# X13_Power_Distribution_C.net
KiCad netlist of a schematic drawn in EAGLE
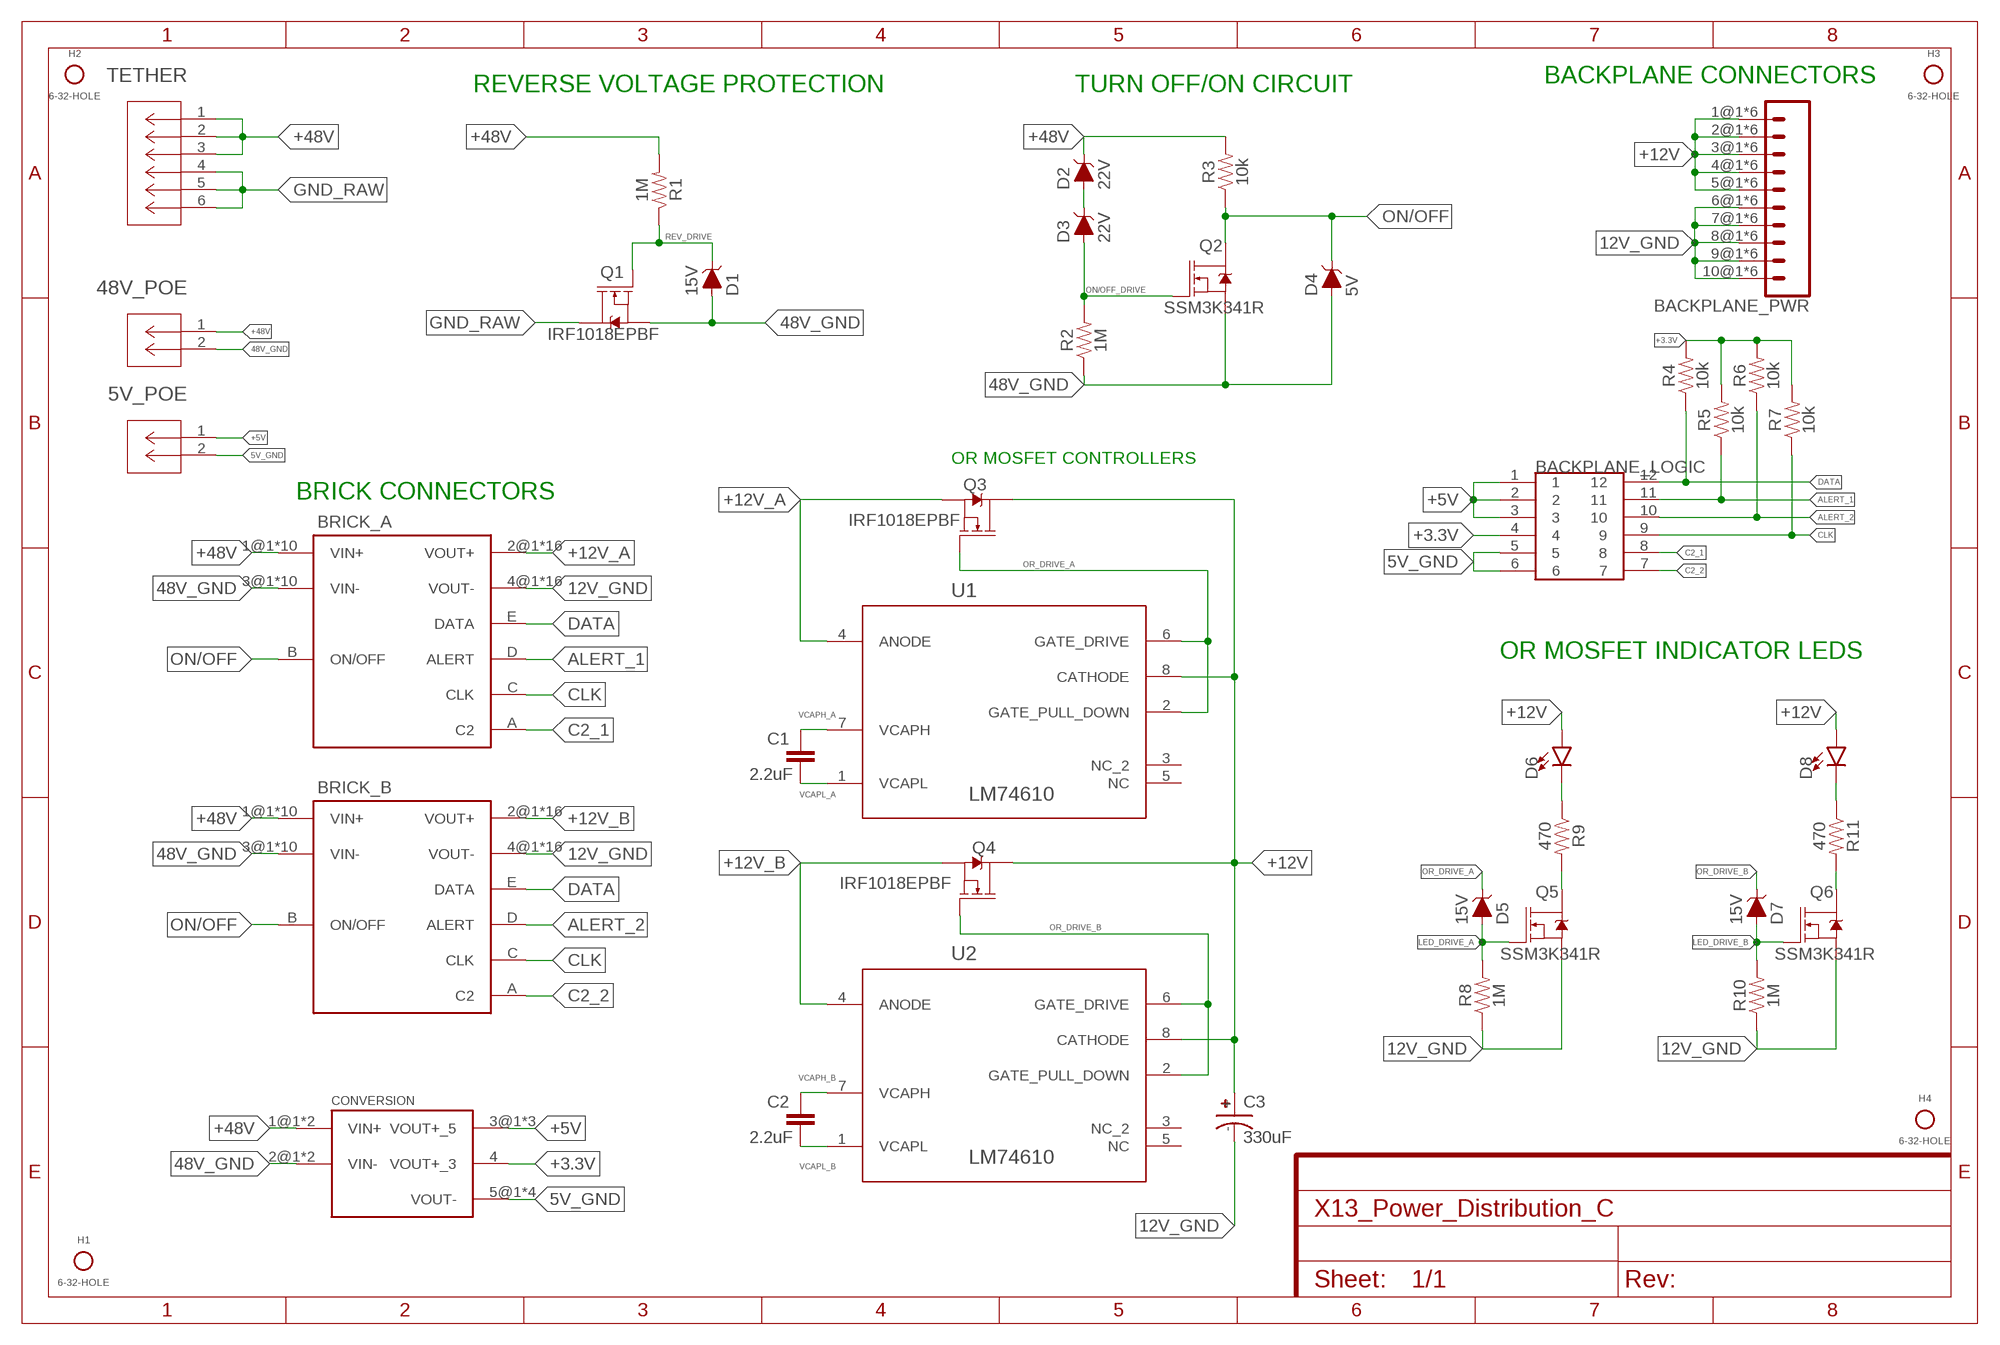
[diagram p0: schematic, sheet 1, part 1 of 2]
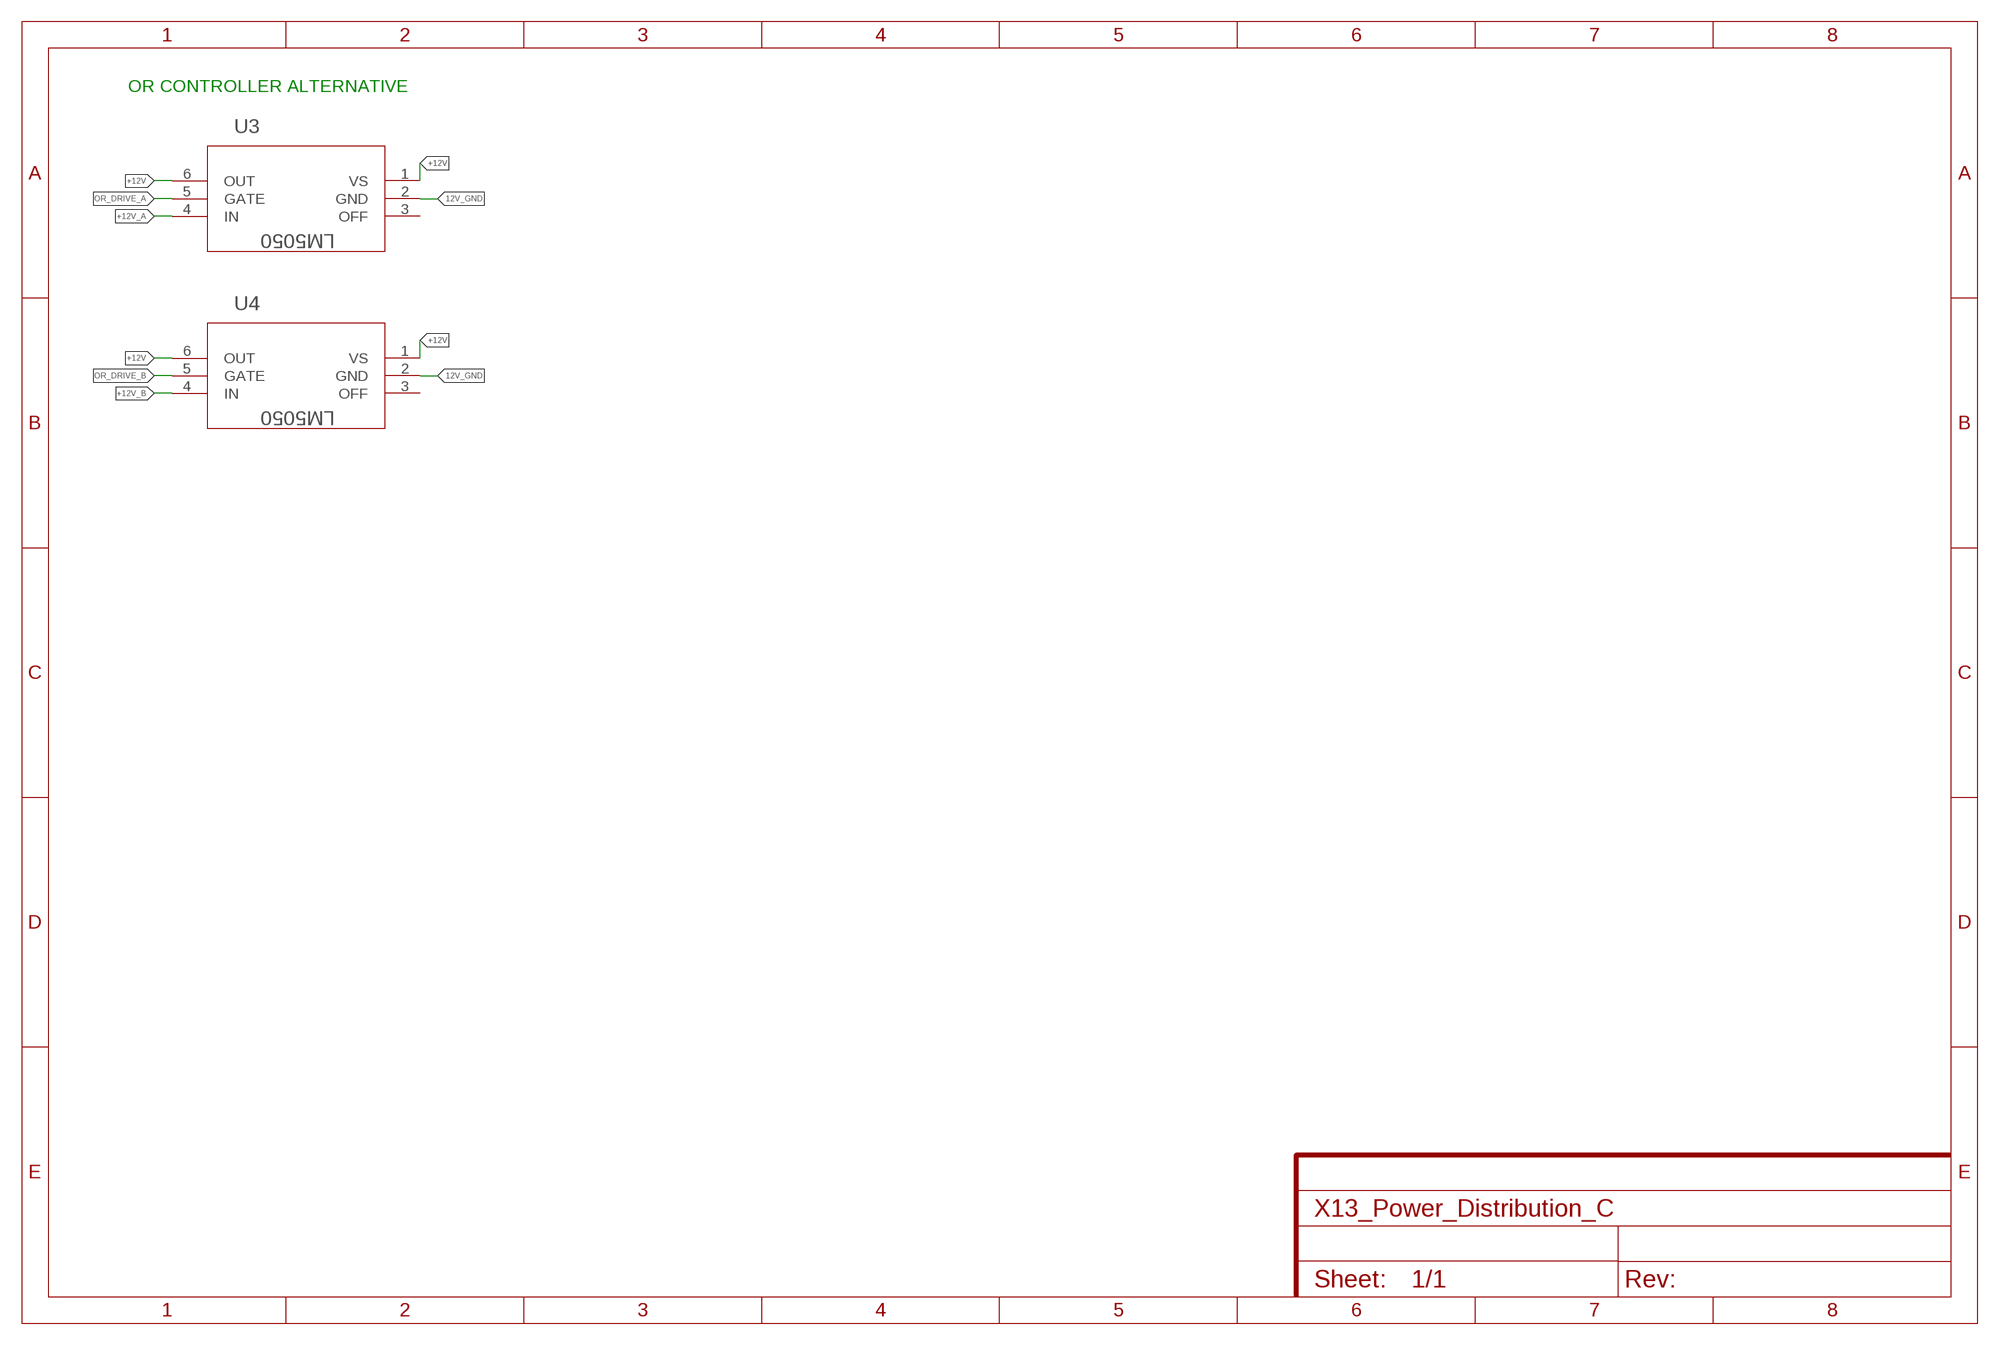
[diagram p1: schematic, sheet 1, part 2 of 2]

(export (version "E")
  (design (tool "Eeschema 10.0.6"))
  (components
    (comp (ref "5V_POE")
      (value "POE_TERMINAL")
      (footprint "eagle-import:CONN2_282834-2_TEC")
      (fields
        (field (name "MANUFACTURER_PART_NUMBER") "282834-2")
        (field (name "COPYRIGHT") "Copyright (C) 2016 Accelerated Designs. All rights reserved")
      )
      (libsource (lib "eagle-import") (part "POE_TERMINAL"))
    )
    (comp (ref "48V_POE")
      (value "POE_TERMINAL")
      (footprint "eagle-import:CONN2_282834-2_TEC")
      (fields
        (field (name "MANUFACTURER_PART_NUMBER") "282834-2")
        (field (name "COPYRIGHT") "Copyright (C) 2016 Accelerated Designs. All rights reserved")
      )
      (libsource (lib "eagle-import") (part "POE_TERMINAL"))
    )
    (comp (ref "BACKPLANE_LOGIC")
      (value "IPL1-106-01-L-D-RE1-K")
      (footprint "eagle-import:IPL1-106-01-L-D-RE1-K")
      (libsource (lib "eagle-import") (part "IPL1-106-01-L-D-RE1-K"))
    )
    (comp (ref "BACKPLANE_PWR")
      (value "MPPT-10-01-01-L-RA-SD")
      (footprint "eagle-import:MPPT-10-01-01-L-RA-SD")
      (libsource (lib "eagle-import") (part "MPPT-10-01-01-L-RA-SD"))
    )
    (comp (ref "BRICK_A")
      (value "DIST2BRICK_C")
      (footprint "eagle-import:DIST2BRICK_C")
      (libsource (lib "eagle-import") (part "DIST2BRICK_C"))
    )
    (comp (ref "BRICK_B")
      (value "DIST2BRICK_C")
      (footprint "eagle-import:DIST2BRICK_C")
      (libsource (lib "eagle-import") (part "DIST2BRICK_C"))
    )
    (comp (ref "C1")
      (value "2.2uF")
      (footprint "eagle-import:0603")
      (libsource (lib "eagle-import") (part "0.1UF-0603-100V-10%"))
    )
    (comp (ref "C2")
      (value "2.2uF")
      (footprint "eagle-import:0603")
      (libsource (lib "eagle-import") (part "0.1UF-0603-100V-10%"))
    )
    (comp (ref "C3")
      (value "330uF")
      (footprint "eagle-import:CAPAE1030X1050N")
      (fields
        (field (name "ARROW_PART_NUMBER") "UCM1H331MNL1GS")
        (field (name "MOUSER_PART_NUMBER") "647-UCM1H331MNL1GS")
      )
      (libsource (lib "eagle-import") (part "UCM1H331MNL1GS"))
    )
    (comp (ref "CONVERSION")
      (value "DIST2CON")
      (footprint "eagle-import:DIST2CON")
      (libsource (lib "eagle-import") (part "DIST2CON"))
    )
    (comp (ref "D1")
      (value "15V")
      (footprint "eagle-import:SOD-323")
      (libsource (lib "eagle-import") (part "DIODE-ZENER-BZT52C3V6S"))
    )
    (comp (ref "D2")
      (value "22V")
      (footprint "eagle-import:SOD-323")
      (libsource (lib "eagle-import") (part "DIODE-ZENER-BZT52C3V6S"))
    )
    (comp (ref "D3")
      (value "22V")
      (footprint "eagle-import:SOD-323")
      (libsource (lib "eagle-import") (part "DIODE-ZENER-BZT52C3V6S"))
    )
    (comp (ref "D4")
      (value "5V")
      (footprint "eagle-import:SOD-323")
      (libsource (lib "eagle-import") (part "DIODE-ZENER-BZT52C3V6S"))
    )
    (comp (ref "D5")
      (value "15V")
      (footprint "eagle-import:SOD-323")
      (libsource (lib "eagle-import") (part "DIODE-ZENER-BZT52C3V6S"))
    )
    (comp (ref "D6")
      (value "LED0603")
      (footprint "eagle-import:LED-0603")
      (libsource (lib "eagle-import") (part "LED0603"))
    )
    (comp (ref "D7")
      (value "15V")
      (footprint "eagle-import:SOD-323")
      (libsource (lib "eagle-import") (part "DIODE-ZENER-BZT52C3V6S"))
    )
    (comp (ref "D8")
      (value "LED0603")
      (footprint "eagle-import:LED-0603")
      (libsource (lib "eagle-import") (part "LED0603"))
    )
    (comp (ref "H1")
      (value "6-32-HOLE")
      (footprint "eagle-import:6-32-HOLE")
      (libsource (lib "eagle-import") (part "6-32-HOLE"))
    )
    (comp (ref "H2")
      (value "6-32-HOLE")
      (footprint "eagle-import:6-32-HOLE")
      (libsource (lib "eagle-import") (part "6-32-HOLE"))
    )
    (comp (ref "H3")
      (value "6-32-HOLE")
      (footprint "eagle-import:6-32-HOLE")
      (libsource (lib "eagle-import") (part "6-32-HOLE"))
    )
    (comp (ref "H4")
      (value "6-32-HOLE")
      (footprint "eagle-import:6-32-HOLE")
      (libsource (lib "eagle-import") (part "6-32-HOLE"))
    )
    (comp (ref "Q1")
      (value "IRF1018EPBF")
      (footprint "eagle-import:TO263")
      (libsource (lib "eagle-import") (part "IRF1018EPBF"))
    )
    (comp (ref "Q2")
      (value "SSM3K341R")
      (footprint "eagle-import:SOT323")
      (libsource (lib "eagle-import") (part "MOSFET-NCH-2N7002PW"))
    )
    (comp (ref "Q3")
      (value "IRF1018EPBF")
      (footprint "eagle-import:TO263")
      (libsource (lib "eagle-import") (part "IRF1018EPBF"))
    )
    (comp (ref "Q4")
      (value "IRF1018EPBF")
      (footprint "eagle-import:TO263")
      (libsource (lib "eagle-import") (part "IRF1018EPBF"))
    )
    (comp (ref "Q5")
      (value "SSM3K341R")
      (footprint "eagle-import:SOT323")
      (libsource (lib "eagle-import") (part "MOSFET-NCH-2N7002PW"))
    )
    (comp (ref "Q6")
      (value "SSM3K341R")
      (footprint "eagle-import:SOT323")
      (libsource (lib "eagle-import") (part "MOSFET-NCH-2N7002PW"))
    )
    (comp (ref "R1")
      (value "1M")
      (footprint "eagle-import:0603")
      (libsource (lib "eagle-import") (part "RESISTOR0603"))
    )
    (comp (ref "R2")
      (value "1M")
      (footprint "eagle-import:0603")
      (fields (field (name "SPICEPREFIX") "R"))
      (libsource (lib "eagle-import") (part "RESISTOR0603"))
    )
    (comp (ref "R3")
      (value "10k")
      (footprint "eagle-import:0603")
      (fields (field (name "SPICEPREFIX") "R"))
      (libsource (lib "eagle-import") (part "RESISTOR0603"))
    )
    (comp (ref "R4")
      (value "10k")
      (footprint "eagle-import:0603")
      (libsource (lib "eagle-import") (part "RESISTOR0603"))
    )
    (comp (ref "R5")
      (value "10k")
      (footprint "eagle-import:0603")
      (libsource (lib "eagle-import") (part "RESISTOR0603"))
    )
    (comp (ref "R6")
      (value "10k")
      (footprint "eagle-import:0603")
      (libsource (lib "eagle-import") (part "RESISTOR0603"))
    )
    (comp (ref "R7")
      (value "10k")
      (footprint "eagle-import:0603")
      (libsource (lib "eagle-import") (part "RESISTOR0603"))
    )
    (comp (ref "R8")
      (value "1M")
      (footprint "eagle-import:0603")
      (fields (field (name "SPICEPREFIX") "R"))
      (libsource (lib "eagle-import") (part "RESISTOR0603"))
    )
    (comp (ref "R9")
      (value "470")
      (footprint "eagle-import:0603")
      (libsource (lib "eagle-import") (part "RESISTOR0603"))
    )
    (comp (ref "R10")
      (value "1M")
      (footprint "eagle-import:0603")
      (fields (field (name "SPICEPREFIX") "R"))
      (libsource (lib "eagle-import") (part "RESISTOR0603"))
    )
    (comp (ref "R11")
      (value "470")
      (footprint "eagle-import:0603")
      (libsource (lib "eagle-import") (part "RESISTOR0603"))
    )
    (comp (ref "TETHER")
      (value "48V")
      (footprint "eagle-import:CON6_P5MM_VER_TERM-BLK_TYC")
      (fields (field (name "MANUFACTURER_PART_NUMBER") "796636-6"))
      (libsource (lib "eagle-import") (part "DIST_TO_TETHER"))
    )
    (comp (ref "U1")
      (value "LM74610")
      (footprint "eagle-import:DGK0008A_M")
      (fields (field (name "MANUFACTURER") "Texas Instruments") (field (name "PARTNUMBER") "LM74610QDGKRQ1"))
      (libsource (lib "eagle-import") (part "DIST_OR_DIODEDGK0008A_M"))
    )
    (comp (ref "U2")
      (value "LM74610")
      (footprint "eagle-import:DGK0008A_M")
      (fields (field (name "MANUFACTURER") "Texas Instruments") (field (name "PARTNUMBER") "LM74610QDGKRQ1"))
      (libsource (lib "eagle-import") (part "DIST_OR_DIODEDGK0008A_M"))
    )
    (comp (ref "U3")
      (value "LM5050")
      (footprint "eagle-import:MK06A-M")
      (fields
        (field (name "MANUFACTURER") "Texas Instruments")
        (field (name "MANUFACTURER_PART_NUMBER") "LM5050MK-1/NOPB")
      )
      (libsource (lib "eagle-import") (part "DIST_OR_CONTROL_ALTMK06A-M"))
    )
    (comp (ref "U4")
      (value "LM5050")
      (footprint "eagle-import:MK06A-M")
      (fields
        (field (name "MANUFACTURER") "Texas Instruments")
        (field (name "MANUFACTURER_PART_NUMBER") "LM5050MK-1/NOPB")
      )
      (libsource (lib "eagle-import") (part "DIST_OR_CONTROL_ALTMK06A-M"))
    )
  )
  (nets
    (net (code "1") (name "+3.3V") (class "Default")
      (node (ref "BACKPLANE_LOGIC") (pin "4") (pinfunction "4_4") (pintype "bidirectional"))
      (node (ref "CONVERSION") (pin "4") (pinfunction "VOUT+_3_4") (pintype "bidirectional"))
      (node (ref "R4") (pin "2") (pinfunction "2_2") (pintype "passive"))
      (node (ref "R5") (pin "2") (pinfunction "2_2") (pintype "passive"))
      (node (ref "R6") (pin "2") (pinfunction "2_2") (pintype "passive"))
      (node (ref "R7") (pin "2") (pinfunction "2_2") (pintype "passive"))
    )
    (net (code "2") (name "+5V") (class "Default")
      (node (ref "5V_POE") (pin "1") (pinfunction "1_1") (pintype "passive"))
      (node (ref "BACKPLANE_LOGIC") (pin "1") (pinfunction "1_1") (pintype "bidirectional"))
      (node (ref "BACKPLANE_LOGIC") (pin "2") (pinfunction "2_2") (pintype "bidirectional"))
      (node (ref "BACKPLANE_LOGIC") (pin "3") (pinfunction "3_3") (pintype "bidirectional"))
      (node (ref "CONVERSION") (pin "3@1") (pinfunction "VOUT+_5_3@1") (pintype "bidirectional"))
      (node (ref "CONVERSION") (pin "3@2") (pinfunction "VOUT+_5_3@2") (pintype "bidirectional"))
      (node (ref "CONVERSION") (pin "3@3") (pinfunction "VOUT+_5_3@3") (pintype "bidirectional"))
    )
    (net (code "3") (name "+12V") (class "Default")
      (node (ref "BACKPLANE_PWR") (pin "1@1") (pinfunction "1_1@1") (pintype "passive"))
      (node (ref "BACKPLANE_PWR") (pin "1@2") (pinfunction "1_1@2") (pintype "passive"))
      (node (ref "BACKPLANE_PWR") (pin "1@3") (pinfunction "1_1@3") (pintype "passive"))
      (node (ref "BACKPLANE_PWR") (pin "1@4") (pinfunction "1_1@4") (pintype "passive"))
      (node (ref "BACKPLANE_PWR") (pin "1@5") (pinfunction "1_1@5") (pintype "passive"))
      (node (ref "BACKPLANE_PWR") (pin "1@6") (pinfunction "1_1@6") (pintype "passive"))
      (node (ref "BACKPLANE_PWR") (pin "2@1") (pinfunction "2_2@1") (pintype "passive"))
      (node (ref "BACKPLANE_PWR") (pin "2@2") (pinfunction "2_2@2") (pintype "passive"))
      (node (ref "BACKPLANE_PWR") (pin "2@3") (pinfunction "2_2@3") (pintype "passive"))
      (node (ref "BACKPLANE_PWR") (pin "2@4") (pinfunction "2_2@4") (pintype "passive"))
      (node (ref "BACKPLANE_PWR") (pin "2@5") (pinfunction "2_2@5") (pintype "passive"))
      (node (ref "BACKPLANE_PWR") (pin "2@6") (pinfunction "2_2@6") (pintype "passive"))
      (node (ref "BACKPLANE_PWR") (pin "3@1") (pinfunction "3_3@1") (pintype "passive"))
      (node (ref "BACKPLANE_PWR") (pin "3@2") (pinfunction "3_3@2") (pintype "passive"))
      (node (ref "BACKPLANE_PWR") (pin "3@3") (pinfunction "3_3@3") (pintype "passive"))
      (node (ref "BACKPLANE_PWR") (pin "3@4") (pinfunction "3_3@4") (pintype "passive"))
      (node (ref "BACKPLANE_PWR") (pin "3@5") (pinfunction "3_3@5") (pintype "passive"))
      (node (ref "BACKPLANE_PWR") (pin "3@6") (pinfunction "3_3@6") (pintype "passive"))
      (node (ref "BACKPLANE_PWR") (pin "4@1") (pinfunction "4_4@1") (pintype "passive"))
      (node (ref "BACKPLANE_PWR") (pin "4@2") (pinfunction "4_4@2") (pintype "passive"))
      (node (ref "BACKPLANE_PWR") (pin "4@3") (pinfunction "4_4@3") (pintype "passive"))
      (node (ref "BACKPLANE_PWR") (pin "4@4") (pinfunction "4_4@4") (pintype "passive"))
      (node (ref "BACKPLANE_PWR") (pin "4@5") (pinfunction "4_4@5") (pintype "passive"))
      (node (ref "BACKPLANE_PWR") (pin "4@6") (pinfunction "4_4@6") (pintype "passive"))
      (node (ref "BACKPLANE_PWR") (pin "5@1") (pinfunction "5_5@1") (pintype "passive"))
      (node (ref "BACKPLANE_PWR") (pin "5@2") (pinfunction "5_5@2") (pintype "passive"))
      (node (ref "BACKPLANE_PWR") (pin "5@3") (pinfunction "5_5@3") (pintype "passive"))
      (node (ref "BACKPLANE_PWR") (pin "5@4") (pinfunction "5_5@4") (pintype "passive"))
      (node (ref "BACKPLANE_PWR") (pin "5@5") (pinfunction "5_5@5") (pintype "passive"))
      (node (ref "BACKPLANE_PWR") (pin "5@6") (pinfunction "5_5@6") (pintype "passive"))
      (node (ref "C3") (pin "+") (pinfunction "+_+") (pintype "bidirectional"))
      (node (ref "D6") (pin "A") (pinfunction "A_A") (pintype "passive"))
      (node (ref "D8") (pin "A") (pinfunction "A_A") (pintype "passive"))
      (node (ref "Q3") (pin "3") (pinfunction "D_3") (pintype "bidirectional"))
      (node (ref "Q4") (pin "3") (pinfunction "D_3") (pintype "bidirectional"))
      (node (ref "U1") (pin "8") (pinfunction "CATHODE_8") (pintype "output"))
      (node (ref "U2") (pin "8") (pinfunction "CATHODE_8") (pintype "output"))
      (node (ref "U3") (pin "1") (pinfunction "VS_1") (pintype "passive"))
      (node (ref "U3") (pin "6") (pinfunction "OUT_6") (pintype "output"))
      (node (ref "U4") (pin "1") (pinfunction "VS_1") (pintype "passive"))
      (node (ref "U4") (pin "6") (pinfunction "OUT_6") (pintype "output"))
    )
    (net (code "4") (name "+12V_A") (class "Default")
      (node (ref "BRICK_A") (pin "2@1") (pinfunction "VOUT+_2@1") (pintype "bidirectional"))
      (node (ref "BRICK_A") (pin "2@10") (pinfunction "VOUT+_2@10") (pintype "bidirectional"))
      (node (ref "BRICK_A") (pin "2@11") (pinfunction "VOUT+_2@11") (pintype "bidirectional"))
      (node (ref "BRICK_A") (pin "2@12") (pinfunction "VOUT+_2@12") (pintype "bidirectional"))
      (node (ref "BRICK_A") (pin "2@13") (pinfunction "VOUT+_2@13") (pintype "bidirectional"))
      (node (ref "BRICK_A") (pin "2@14") (pinfunction "VOUT+_2@14") (pintype "bidirectional"))
      (node (ref "BRICK_A") (pin "2@15") (pinfunction "VOUT+_2@15") (pintype "bidirectional"))
      (node (ref "BRICK_A") (pin "2@16") (pinfunction "VOUT+_2@16") (pintype "bidirectional"))
      (node (ref "BRICK_A") (pin "2@2") (pinfunction "VOUT+_2@2") (pintype "bidirectional"))
      (node (ref "BRICK_A") (pin "2@3") (pinfunction "VOUT+_2@3") (pintype "bidirectional"))
      (node (ref "BRICK_A") (pin "2@4") (pinfunction "VOUT+_2@4") (pintype "bidirectional"))
      (node (ref "BRICK_A") (pin "2@5") (pinfunction "VOUT+_2@5") (pintype "bidirectional"))
      (node (ref "BRICK_A") (pin "2@6") (pinfunction "VOUT+_2@6") (pintype "bidirectional"))
      (node (ref "BRICK_A") (pin "2@7") (pinfunction "VOUT+_2@7") (pintype "bidirectional"))
      (node (ref "BRICK_A") (pin "2@8") (pinfunction "VOUT+_2@8") (pintype "bidirectional"))
      (node (ref "BRICK_A") (pin "2@9") (pinfunction "VOUT+_2@9") (pintype "bidirectional"))
      (node (ref "Q3") (pin "2") (pinfunction "S_2") (pintype "bidirectional"))
      (node (ref "U1") (pin "4") (pinfunction "ANODE_4") (pintype "power_in"))
      (node (ref "U3") (pin "4") (pinfunction "IN_4") (pintype "input"))
    )
    (net (code "5") (name "+12V_B") (class "Default")
      (node (ref "BRICK_B") (pin "2@1") (pinfunction "VOUT+_2@1") (pintype "bidirectional"))
      (node (ref "BRICK_B") (pin "2@10") (pinfunction "VOUT+_2@10") (pintype "bidirectional"))
      (node (ref "BRICK_B") (pin "2@11") (pinfunction "VOUT+_2@11") (pintype "bidirectional"))
      (node (ref "BRICK_B") (pin "2@12") (pinfunction "VOUT+_2@12") (pintype "bidirectional"))
      (node (ref "BRICK_B") (pin "2@13") (pinfunction "VOUT+_2@13") (pintype "bidirectional"))
      (node (ref "BRICK_B") (pin "2@14") (pinfunction "VOUT+_2@14") (pintype "bidirectional"))
      (node (ref "BRICK_B") (pin "2@15") (pinfunction "VOUT+_2@15") (pintype "bidirectional"))
      (node (ref "BRICK_B") (pin "2@16") (pinfunction "VOUT+_2@16") (pintype "bidirectional"))
      (node (ref "BRICK_B") (pin "2@2") (pinfunction "VOUT+_2@2") (pintype "bidirectional"))
      (node (ref "BRICK_B") (pin "2@3") (pinfunction "VOUT+_2@3") (pintype "bidirectional"))
      (node (ref "BRICK_B") (pin "2@4") (pinfunction "VOUT+_2@4") (pintype "bidirectional"))
      (node (ref "BRICK_B") (pin "2@5") (pinfunction "VOUT+_2@5") (pintype "bidirectional"))
      (node (ref "BRICK_B") (pin "2@6") (pinfunction "VOUT+_2@6") (pintype "bidirectional"))
      (node (ref "BRICK_B") (pin "2@7") (pinfunction "VOUT+_2@7") (pintype "bidirectional"))
      (node (ref "BRICK_B") (pin "2@8") (pinfunction "VOUT+_2@8") (pintype "bidirectional"))
      (node (ref "BRICK_B") (pin "2@9") (pinfunction "VOUT+_2@9") (pintype "bidirectional"))
      (node (ref "Q4") (pin "2") (pinfunction "S_2") (pintype "bidirectional"))
      (node (ref "U2") (pin "4") (pinfunction "ANODE_4") (pintype "power_in"))
      (node (ref "U4") (pin "4") (pinfunction "IN_4") (pintype "input"))
    )
    (net (code "6") (name "+48V") (class "Default")
      (node (ref "48V_POE") (pin "1") (pinfunction "1_1") (pintype "passive"))
      (node (ref "BRICK_A") (pin "1@1") (pinfunction "VIN+_1@1") (pintype "bidirectional"))
      (node (ref "BRICK_A") (pin "1@10") (pinfunction "VIN+_1@10") (pintype "bidirectional"))
      (node (ref "BRICK_A") (pin "1@2") (pinfunction "VIN+_1@2") (pintype "bidirectional"))
      (node (ref "BRICK_A") (pin "1@3") (pinfunction "VIN+_1@3") (pintype "bidirectional"))
      (node (ref "BRICK_A") (pin "1@4") (pinfunction "VIN+_1@4") (pintype "bidirectional"))
      (node (ref "BRICK_A") (pin "1@5") (pinfunction "VIN+_1@5") (pintype "bidirectional"))
      (node (ref "BRICK_A") (pin "1@6") (pinfunction "VIN+_1@6") (pintype "bidirectional"))
      (node (ref "BRICK_A") (pin "1@7") (pinfunction "VIN+_1@7") (pintype "bidirectional"))
      (node (ref "BRICK_A") (pin "1@8") (pinfunction "VIN+_1@8") (pintype "bidirectional"))
      (node (ref "BRICK_A") (pin "1@9") (pinfunction "VIN+_1@9") (pintype "bidirectional"))
      (node (ref "BRICK_B") (pin "1@1") (pinfunction "VIN+_1@1") (pintype "bidirectional"))
      (node (ref "BRICK_B") (pin "1@10") (pinfunction "VIN+_1@10") (pintype "bidirectional"))
      (node (ref "BRICK_B") (pin "1@2") (pinfunction "VIN+_1@2") (pintype "bidirectional"))
      (node (ref "BRICK_B") (pin "1@3") (pinfunction "VIN+_1@3") (pintype "bidirectional"))
      (node (ref "BRICK_B") (pin "1@4") (pinfunction "VIN+_1@4") (pintype "bidirectional"))
      (node (ref "BRICK_B") (pin "1@5") (pinfunction "VIN+_1@5") (pintype "bidirectional"))
      (node (ref "BRICK_B") (pin "1@6") (pinfunction "VIN+_1@6") (pintype "bidirectional"))
      (node (ref "BRICK_B") (pin "1@7") (pinfunction "VIN+_1@7") (pintype "bidirectional"))
      (node (ref "BRICK_B") (pin "1@8") (pinfunction "VIN+_1@8") (pintype "bidirectional"))
      (node (ref "BRICK_B") (pin "1@9") (pinfunction "VIN+_1@9") (pintype "bidirectional"))
      (node (ref "CONVERSION") (pin "1@1") (pinfunction "VIN+_1@1") (pintype "bidirectional"))
      (node (ref "CONVERSION") (pin "1@2") (pinfunction "VIN+_1@2") (pintype "bidirectional"))
      (node (ref "D2") (pin "C") (pinfunction "C_C") (pintype "passive"))
      (node (ref "R1") (pin "2") (pinfunction "2_2") (pintype "passive"))
      (node (ref "R3") (pin "2") (pinfunction "2_2") (pintype "passive"))
      (node (ref "TETHER") (pin "1") (pinfunction "1_1") (pintype "passive"))
      (node (ref "TETHER") (pin "2") (pinfunction "2_2") (pintype "passive"))
      (node (ref "TETHER") (pin "3") (pinfunction "3_3") (pintype "passive"))
    )
    (net (code "7") (name "/ON{slash}OFF_DRIVE") (class "Default")
      (node (ref "D3") (pin "A") (pinfunction "A_A") (pintype "passive"))
      (node (ref "Q2") (pin "1") (pinfunction "G_1") (pintype "bidirectional"))
      (node (ref "R2") (pin "2") (pinfunction "2_2") (pintype "passive"))
    )
    (net (code "8") (name "/REV_DRIVE") (class "Default")
      (node (ref "D1") (pin "C") (pinfunction "C_C") (pintype "passive"))
      (node (ref "Q1") (pin "1") (pinfunction "G_1") (pintype "bidirectional"))
      (node (ref "R1") (pin "1") (pinfunction "1_1") (pintype "passive"))
    )
    (net (code "9") (name "/VCAPH_A") (class "Default")
      (node (ref "C1") (pin "1") (pinfunction "1_1") (pintype "passive"))
      (node (ref "U1") (pin "7") (pinfunction "VCAPH_7") (pintype "passive"))
    )
    (net (code "10") (name "/VCAPH_B") (class "Default")
      (node (ref "C2") (pin "1") (pinfunction "1_1") (pintype "passive"))
      (node (ref "U2") (pin "7") (pinfunction "VCAPH_7") (pintype "passive"))
    )
    (net (code "11") (name "/VCAPL_A") (class "Default")
      (node (ref "C1") (pin "2") (pinfunction "2_2") (pintype "passive"))
      (node (ref "U1") (pin "1") (pinfunction "VCAPL_1") (pintype "passive"))
    )
    (net (code "12") (name "/VCAPL_B") (class "Default")
      (node (ref "C2") (pin "2") (pinfunction "2_2") (pintype "passive"))
      (node (ref "U2") (pin "1") (pinfunction "VCAPL_1") (pintype "passive"))
    )
    (net (code "13") (name "5V_GND") (class "Default")
      (node (ref "5V_POE") (pin "2") (pinfunction "2_2") (pintype "passive"))
      (node (ref "BACKPLANE_LOGIC") (pin "5") (pinfunction "5_5") (pintype "bidirectional"))
      (node (ref "BACKPLANE_LOGIC") (pin "6") (pinfunction "6_6") (pintype "bidirectional"))
      (node (ref "CONVERSION") (pin "5@1") (pinfunction "VOUT-_5@1") (pintype "bidirectional"))
      (node (ref "CONVERSION") (pin "5@2") (pinfunction "VOUT-_5@2") (pintype "bidirectional"))
      (node (ref "CONVERSION") (pin "5@3") (pinfunction "VOUT-_5@3") (pintype "bidirectional"))
      (node (ref "CONVERSION") (pin "5@4") (pinfunction "VOUT-_5@4") (pintype "bidirectional"))
    )
    (net (code "14") (name "12V_GND") (class "Default")
      (node (ref "BACKPLANE_PWR") (pin "10@1") (pinfunction "10_10@1") (pintype "passive"))
      (node (ref "BACKPLANE_PWR") (pin "10@2") (pinfunction "10_10@2") (pintype "passive"))
      (node (ref "BACKPLANE_PWR") (pin "10@3") (pinfunction "10_10@3") (pintype "passive"))
      (node (ref "BACKPLANE_PWR") (pin "10@4") (pinfunction "10_10@4") (pintype "passive"))
      (node (ref "BACKPLANE_PWR") (pin "10@5") (pinfunction "10_10@5") (pintype "passive"))
      (node (ref "BACKPLANE_PWR") (pin "10@6") (pinfunction "10_10@6") (pintype "passive"))
      (node (ref "BACKPLANE_PWR") (pin "6@1") (pinfunction "6_6@1") (pintype "passive"))
      (node (ref "BACKPLANE_PWR") (pin "6@2") (pinfunction "6_6@2") (pintype "passive"))
      (node (ref "BACKPLANE_PWR") (pin "6@3") (pinfunction "6_6@3") (pintype "passive"))
      (node (ref "BACKPLANE_PWR") (pin "6@4") (pinfunction "6_6@4") (pintype "passive"))
      (node (ref "BACKPLANE_PWR") (pin "6@5") (pinfunction "6_6@5") (pintype "passive"))
      (node (ref "BACKPLANE_PWR") (pin "6@6") (pinfunction "6_6@6") (pintype "passive"))
      (node (ref "BACKPLANE_PWR") (pin "7@1") (pinfunction "7_7@1") (pintype "passive"))
      (node (ref "BACKPLANE_PWR") (pin "7@2") (pinfunction "7_7@2") (pintype "passive"))
      (node (ref "BACKPLANE_PWR") (pin "7@3") (pinfunction "7_7@3") (pintype "passive"))
      (node (ref "BACKPLANE_PWR") (pin "7@4") (pinfunction "7_7@4") (pintype "passive"))
      (node (ref "BACKPLANE_PWR") (pin "7@5") (pinfunction "7_7@5") (pintype "passive"))
      (node (ref "BACKPLANE_PWR") (pin "7@6") (pinfunction "7_7@6") (pintype "passive"))
      (node (ref "BACKPLANE_PWR") (pin "8@1") (pinfunction "8_8@1") (pintype "passive"))
      (node (ref "BACKPLANE_PWR") (pin "8@2") (pinfunction "8_8@2") (pintype "passive"))
      (node (ref "BACKPLANE_PWR") (pin "8@3") (pinfunction "8_8@3") (pintype "passive"))
      (node (ref "BACKPLANE_PWR") (pin "8@4") (pinfunction "8_8@4") (pintype "passive"))
      (node (ref "BACKPLANE_PWR") (pin "8@5") (pinfunction "8_8@5") (pintype "passive"))
      (node (ref "BACKPLANE_PWR") (pin "8@6") (pinfunction "8_8@6") (pintype "passive"))
      (node (ref "BACKPLANE_PWR") (pin "9@1") (pinfunction "9_9@1") (pintype "passive"))
      (node (ref "BACKPLANE_PWR") (pin "9@2") (pinfunction "9_9@2") (pintype "passive"))
      (node (ref "BACKPLANE_PWR") (pin "9@3") (pinfunction "9_9@3") (pintype "passive"))
      (node (ref "BACKPLANE_PWR") (pin "9@4") (pinfunction "9_9@4") (pintype "passive"))
      (node (ref "BACKPLANE_PWR") (pin "9@5") (pinfunction "9_9@5") (pintype "passive"))
      (node (ref "BACKPLANE_PWR") (pin "9@6") (pinfunction "9_9@6") (pintype "passive"))
      (node (ref "BRICK_A") (pin "4@1") (pinfunction "VOUT-_4@1") (pintype "bidirectional"))
      (node (ref "BRICK_A") (pin "4@10") (pinfunction "VOUT-_4@10") (pintype "bidirectional"))
      (node (ref "BRICK_A") (pin "4@11") (pinfunction "VOUT-_4@11") (pintype "bidirectional"))
      (node (ref "BRICK_A") (pin "4@12") (pinfunction "VOUT-_4@12") (pintype "bidirectional"))
      (node (ref "BRICK_A") (pin "4@13") (pinfunction "VOUT-_4@13") (pintype "bidirectional"))
      (node (ref "BRICK_A") (pin "4@14") (pinfunction "VOUT-_4@14") (pintype "bidirectional"))
      (node (ref "BRICK_A") (pin "4@15") (pinfunction "VOUT-_4@15") (pintype "bidirectional"))
      (node (ref "BRICK_A") (pin "4@16") (pinfunction "VOUT-_4@16") (pintype "bidirectional"))
      (node (ref "BRICK_A") (pin "4@2") (pinfunction "VOUT-_4@2") (pintype "bidirectional"))
      (node (ref "BRICK_A") (pin "4@3") (pinfunction "VOUT-_4@3") (pintype "bidirectional"))
      (node (ref "BRICK_A") (pin "4@4") (pinfunction "VOUT-_4@4") (pintype "bidirectional"))
      (node (ref "BRICK_A") (pin "4@5") (pinfunction "VOUT-_4@5") (pintype "bidirectional"))
      (node (ref "BRICK_A") (pin "4@6") (pinfunction "VOUT-_4@6") (pintype "bidirectional"))
      (node (ref "BRICK_A") (pin "4@7") (pinfunction "VOUT-_4@7") (pintype "bidirectional"))
      (node (ref "BRICK_A") (pin "4@8") (pinfunction "VOUT-_4@8") (pintype "bidirectional"))
      (node (ref "BRICK_A") (pin "4@9") (pinfunction "VOUT-_4@9") (pintype "bidirectional"))
      (node (ref "BRICK_B") (pin "4@1") (pinfunction "VOUT-_4@1") (pintype "bidirectional"))
      (node (ref "BRICK_B") (pin "4@10") (pinfunction "VOUT-_4@10") (pintype "bidirectional"))
      (node (ref "BRICK_B") (pin "4@11") (pinfunction "VOUT-_4@11") (pintype "bidirectional"))
      (node (ref "BRICK_B") (pin "4@12") (pinfunction "VOUT-_4@12") (pintype "bidirectional"))
      (node (ref "BRICK_B") (pin "4@13") (pinfunction "VOUT-_4@13") (pintype "bidirectional"))
      (node (ref "BRICK_B") (pin "4@14") (pinfunction "VOUT-_4@14") (pintype "bidirectional"))
      (node (ref "BRICK_B") (pin "4@15") (pinfunction "VOUT-_4@15") (pintype "bidirectional"))
      (node (ref "BRICK_B") (pin "4@16") (pinfunction "VOUT-_4@16") (pintype "bidirectional"))
      (node (ref "BRICK_B") (pin "4@2") (pinfunction "VOUT-_4@2") (pintype "bidirectional"))
      (node (ref "BRICK_B") (pin "4@3") (pinfunction "VOUT-_4@3") (pintype "bidirectional"))
      (node (ref "BRICK_B") (pin "4@4") (pinfunction "VOUT-_4@4") (pintype "bidirectional"))
      (node (ref "BRICK_B") (pin "4@5") (pinfunction "VOUT-_4@5") (pintype "bidirectional"))
      (node (ref "BRICK_B") (pin "4@6") (pinfunction "VOUT-_4@6") (pintype "bidirectional"))
      (node (ref "BRICK_B") (pin "4@7") (pinfunction "VOUT-_4@7") (pintype "bidirectional"))
      (node (ref "BRICK_B") (pin "4@8") (pinfunction "VOUT-_4@8") (pintype "bidirectional"))
      (node (ref "BRICK_B") (pin "4@9") (pinfunction "VOUT-_4@9") (pintype "bidirectional"))
      (node (ref "C3") (pin "-") (pinfunction "-_-") (pintype "bidirectional"))
      (node (ref "Q5") (pin "2") (pinfunction "S_2") (pintype "bidirectional"))
      (node (ref "Q6") (pin "2") (pinfunction "S_2") (pintype "bidirectional"))
      (node (ref "R10") (pin "1") (pinfunction "1_1") (pintype "passive"))
      (node (ref "R8") (pin "1") (pinfunction "1_1") (pintype "passive"))
      (node (ref "U3") (pin "2") (pinfunction "GND_2") (pintype "power_in"))
      (node (ref "U4") (pin "2") (pinfunction "GND_2") (pintype "power_in"))
    )
    (net (code "15") (name "48V_GND") (class "Default")
      (node (ref "48V_POE") (pin "2") (pinfunction "2_2") (pintype "passive"))
      (node (ref "BRICK_A") (pin "3@1") (pinfunction "VIN-_3@1") (pintype "bidirectional"))
      (node (ref "BRICK_A") (pin "3@10") (pinfunction "VIN-_3@10") (pintype "bidirectional"))
      (node (ref "BRICK_A") (pin "3@2") (pinfunction "VIN-_3@2") (pintype "bidirectional"))
      (node (ref "BRICK_A") (pin "3@3") (pinfunction "VIN-_3@3") (pintype "bidirectional"))
      (node (ref "BRICK_A") (pin "3@4") (pinfunction "VIN-_3@4") (pintype "bidirectional"))
      (node (ref "BRICK_A") (pin "3@5") (pinfunction "VIN-_3@5") (pintype "bidirectional"))
      (node (ref "BRICK_A") (pin "3@6") (pinfunction "VIN-_3@6") (pintype "bidirectional"))
      (node (ref "BRICK_A") (pin "3@7") (pinfunction "VIN-_3@7") (pintype "bidirectional"))
      (node (ref "BRICK_A") (pin "3@8") (pinfunction "VIN-_3@8") (pintype "bidirectional"))
      (node (ref "BRICK_A") (pin "3@9") (pinfunction "VIN-_3@9") (pintype "bidirectional"))
      (node (ref "BRICK_B") (pin "3@1") (pinfunction "VIN-_3@1") (pintype "bidirectional"))
      (node (ref "BRICK_B") (pin "3@10") (pinfunction "VIN-_3@10") (pintype "bidirectional"))
      (node (ref "BRICK_B") (pin "3@2") (pinfunction "VIN-_3@2") (pintype "bidirectional"))
      (node (ref "BRICK_B") (pin "3@3") (pinfunction "VIN-_3@3") (pintype "bidirectional"))
      (node (ref "BRICK_B") (pin "3@4") (pinfunction "VIN-_3@4") (pintype "bidirectional"))
      (node (ref "BRICK_B") (pin "3@5") (pinfunction "VIN-_3@5") (pintype "bidirectional"))
      (node (ref "BRICK_B") (pin "3@6") (pinfunction "VIN-_3@6") (pintype "bidirectional"))
      (node (ref "BRICK_B") (pin "3@7") (pinfunction "VIN-_3@7") (pintype "bidirectional"))
      (node (ref "BRICK_B") (pin "3@8") (pinfunction "VIN-_3@8") (pintype "bidirectional"))
      (node (ref "BRICK_B") (pin "3@9") (pinfunction "VIN-_3@9") (pintype "bidirectional"))
      (node (ref "CONVERSION") (pin "2@1") (pinfunction "VIN-_2@1") (pintype "bidirectional"))
      (node (ref "CONVERSION") (pin "2@2") (pinfunction "VIN-_2@2") (pintype "bidirectional"))
      (node (ref "D1") (pin "A") (pinfunction "A_A") (pintype "passive"))
      (node (ref "D4") (pin "A") (pinfunction "A_A") (pintype "passive"))
      (node (ref "Q1") (pin "2") (pinfunction "S_2") (pintype "bidirectional"))
      (node (ref "Q2") (pin "2") (pinfunction "S_2") (pintype "bidirectional"))
      (node (ref "R2") (pin "1") (pinfunction "1_1") (pintype "passive"))
    )
    (net (code "16") (name "ALERT_1") (class "Default")
      (node (ref "BACKPLANE_LOGIC") (pin "11") (pinfunction "11_11") (pintype "bidirectional"))
      (node (ref "BRICK_A") (pin "D") (pinfunction "ALERT_D") (pintype "bidirectional"))
      (node (ref "R5") (pin "1") (pinfunction "1_1") (pintype "passive"))
    )
    (net (code "17") (name "ALERT_2") (class "Default")
      (node (ref "BACKPLANE_LOGIC") (pin "10") (pinfunction "10_10") (pintype "bidirectional"))
      (node (ref "BRICK_B") (pin "D") (pinfunction "ALERT_D") (pintype "bidirectional"))
      (node (ref "R6") (pin "1") (pinfunction "1_1") (pintype "passive"))
    )
    (net (code "18") (name "C2_1") (class "Default")
      (node (ref "BACKPLANE_LOGIC") (pin "8") (pinfunction "8_8") (pintype "bidirectional"))
      (node (ref "BRICK_A") (pin "A") (pinfunction "C2_A") (pintype "bidirectional"))
    )
    (net (code "19") (name "C2_2") (class "Default")
      (node (ref "BACKPLANE_LOGIC") (pin "7") (pinfunction "7_7") (pintype "bidirectional"))
      (node (ref "BRICK_B") (pin "A") (pinfunction "C2_A") (pintype "bidirectional"))
    )
    (net (code "20") (name "CLK") (class "Default")
      (node (ref "BACKPLANE_LOGIC") (pin "9") (pinfunction "9_9") (pintype "bidirectional"))
      (node (ref "BRICK_A") (pin "C") (pinfunction "CLK_C") (pintype "bidirectional"))
      (node (ref "BRICK_B") (pin "C") (pinfunction "CLK_C") (pintype "bidirectional"))
      (node (ref "R7") (pin "1") (pinfunction "1_1") (pintype "passive"))
    )
    (net (code "21") (name "DATA") (class "Default")
      (node (ref "BACKPLANE_LOGIC") (pin "12") (pinfunction "12_12") (pintype "bidirectional"))
      (node (ref "BRICK_A") (pin "E") (pinfunction "DATA_E") (pintype "bidirectional"))
      (node (ref "BRICK_B") (pin "E") (pinfunction "DATA_E") (pintype "bidirectional"))
      (node (ref "R4") (pin "1") (pinfunction "1_1") (pintype "passive"))
    )
    (net (code "22") (name "GND_RAW") (class "Default")
      (node (ref "Q1") (pin "3") (pinfunction "D_3") (pintype "bidirectional"))
      (node (ref "TETHER") (pin "4") (pinfunction "4_4") (pintype "passive"))
      (node (ref "TETHER") (pin "5") (pinfunction "5_5") (pintype "passive"))
      (node (ref "TETHER") (pin "6") (pinfunction "6_6") (pintype "passive"))
    )
    (net (code "23") (name "LED_DRIVE_A") (class "Default")
      (node (ref "D5") (pin "A") (pinfunction "A_A") (pintype "passive"))
      (node (ref "Q5") (pin "1") (pinfunction "G_1") (pintype "bidirectional"))
      (node (ref "R8") (pin "2") (pinfunction "2_2") (pintype "passive"))
    )
    (net (code "24") (name "LED_DRIVE_B") (class "Default")
      (node (ref "D7") (pin "A") (pinfunction "A_A") (pintype "passive"))
      (node (ref "Q6") (pin "1") (pinfunction "G_1") (pintype "bidirectional"))
      (node (ref "R10") (pin "2") (pinfunction "2_2") (pintype "passive"))
    )
    (net (code "25") (name "Net-(D2-PadA)") (class "Default")
      (node (ref "D2") (pin "A") (pinfunction "A_A") (pintype "passive"))
      (node (ref "D3") (pin "C") (pinfunction "C_C") (pintype "passive"))
    )
    (net (code "26") (name "Net-(D6-PadC)") (class "Default")
      (node (ref "D6") (pin "C") (pinfunction "C_C") (pintype "passive"))
      (node (ref "R9") (pin "1") (pinfunction "1_1") (pintype "passive"))
    )
    (net (code "27") (name "Net-(D8-PadC)") (class "Default")
      (node (ref "D8") (pin "C") (pinfunction "C_C") (pintype "passive"))
      (node (ref "R11") (pin "1") (pinfunction "1_1") (pintype "passive"))
    )
    (net (code "28") (name "Net-(Q5-D)") (class "Default")
      (node (ref "Q5") (pin "3") (pinfunction "D_3") (pintype "bidirectional"))
      (node (ref "R9") (pin "2") (pinfunction "2_2") (pintype "passive"))
    )
    (net (code "29") (name "Net-(Q6-D)") (class "Default")
      (node (ref "Q6") (pin "3") (pinfunction "D_3") (pintype "bidirectional"))
      (node (ref "R11") (pin "2") (pinfunction "2_2") (pintype "passive"))
    )
    (net (code "30") (name "ON{slash}OFF") (class "Default")
      (node (ref "BRICK_A") (pin "B") (pinfunction "ON/OFF_B") (pintype "bidirectional"))
      (node (ref "BRICK_B") (pin "B") (pinfunction "ON/OFF_B") (pintype "bidirectional"))
      (node (ref "D4") (pin "C") (pinfunction "C_C") (pintype "passive"))
      (node (ref "Q2") (pin "3") (pinfunction "D_3") (pintype "bidirectional"))
      (node (ref "R3") (pin "1") (pinfunction "1_1") (pintype "passive"))
    )
    (net (code "31") (name "OR_DRIVE_A") (class "Default")
      (node (ref "D5") (pin "C") (pinfunction "C_C") (pintype "passive"))
      (node (ref "Q3") (pin "1") (pinfunction "G_1") (pintype "bidirectional"))
      (node (ref "U1") (pin "2") (pinfunction "GATE_PULL_DOWN_2") (pintype "passive"))
      (node (ref "U1") (pin "6") (pinfunction "GATE_DRIVE_6") (pintype "output"))
      (node (ref "U3") (pin "5") (pinfunction "GATE_5") (pintype "passive"))
    )
    (net (code "32") (name "OR_DRIVE_B") (class "Default")
      (node (ref "D7") (pin "C") (pinfunction "C_C") (pintype "passive"))
      (node (ref "Q4") (pin "1") (pinfunction "G_1") (pintype "bidirectional"))
      (node (ref "U2") (pin "2") (pinfunction "GATE_PULL_DOWN_2") (pintype "passive"))
      (node (ref "U2") (pin "6") (pinfunction "GATE_DRIVE_6") (pintype "output"))
      (node (ref "U4") (pin "5") (pinfunction "GATE_5") (pintype "passive"))
    )
    (net (code "33") (name "unconnected-(U1-NC-Pad5)") (class "Default")
      (node (ref "U1") (pin "5") (pinfunction "NC_5") (pintype "passive"))
    )
    (net (code "34") (name "unconnected-(U1-NC_2-Pad3)") (class "Default")
      (node (ref "U1") (pin "3") (pinfunction "NC_2_3") (pintype "passive"))
    )
    (net (code "35") (name "unconnected-(U2-NC-Pad5)") (class "Default")
      (node (ref "U2") (pin "5") (pinfunction "NC_5") (pintype "passive"))
    )
    (net (code "36") (name "unconnected-(U2-NC_2-Pad3)") (class "Default")
      (node (ref "U2") (pin "3") (pinfunction "NC_2_3") (pintype "passive"))
    )
    (net (code "37") (name "unconnected-(U3-OFF-Pad3)") (class "Default")
      (node (ref "U3") (pin "3") (pinfunction "OFF_3") (pintype "passive"))
    )
    (net (code "38") (name "unconnected-(U4-OFF-Pad3)") (class "Default")
      (node (ref "U4") (pin "3") (pinfunction "OFF_3") (pintype "passive"))
    )
  )
)
